# PacBot_Official_Schematic.net
KiCad netlist of a schematic drawn in EAGLE
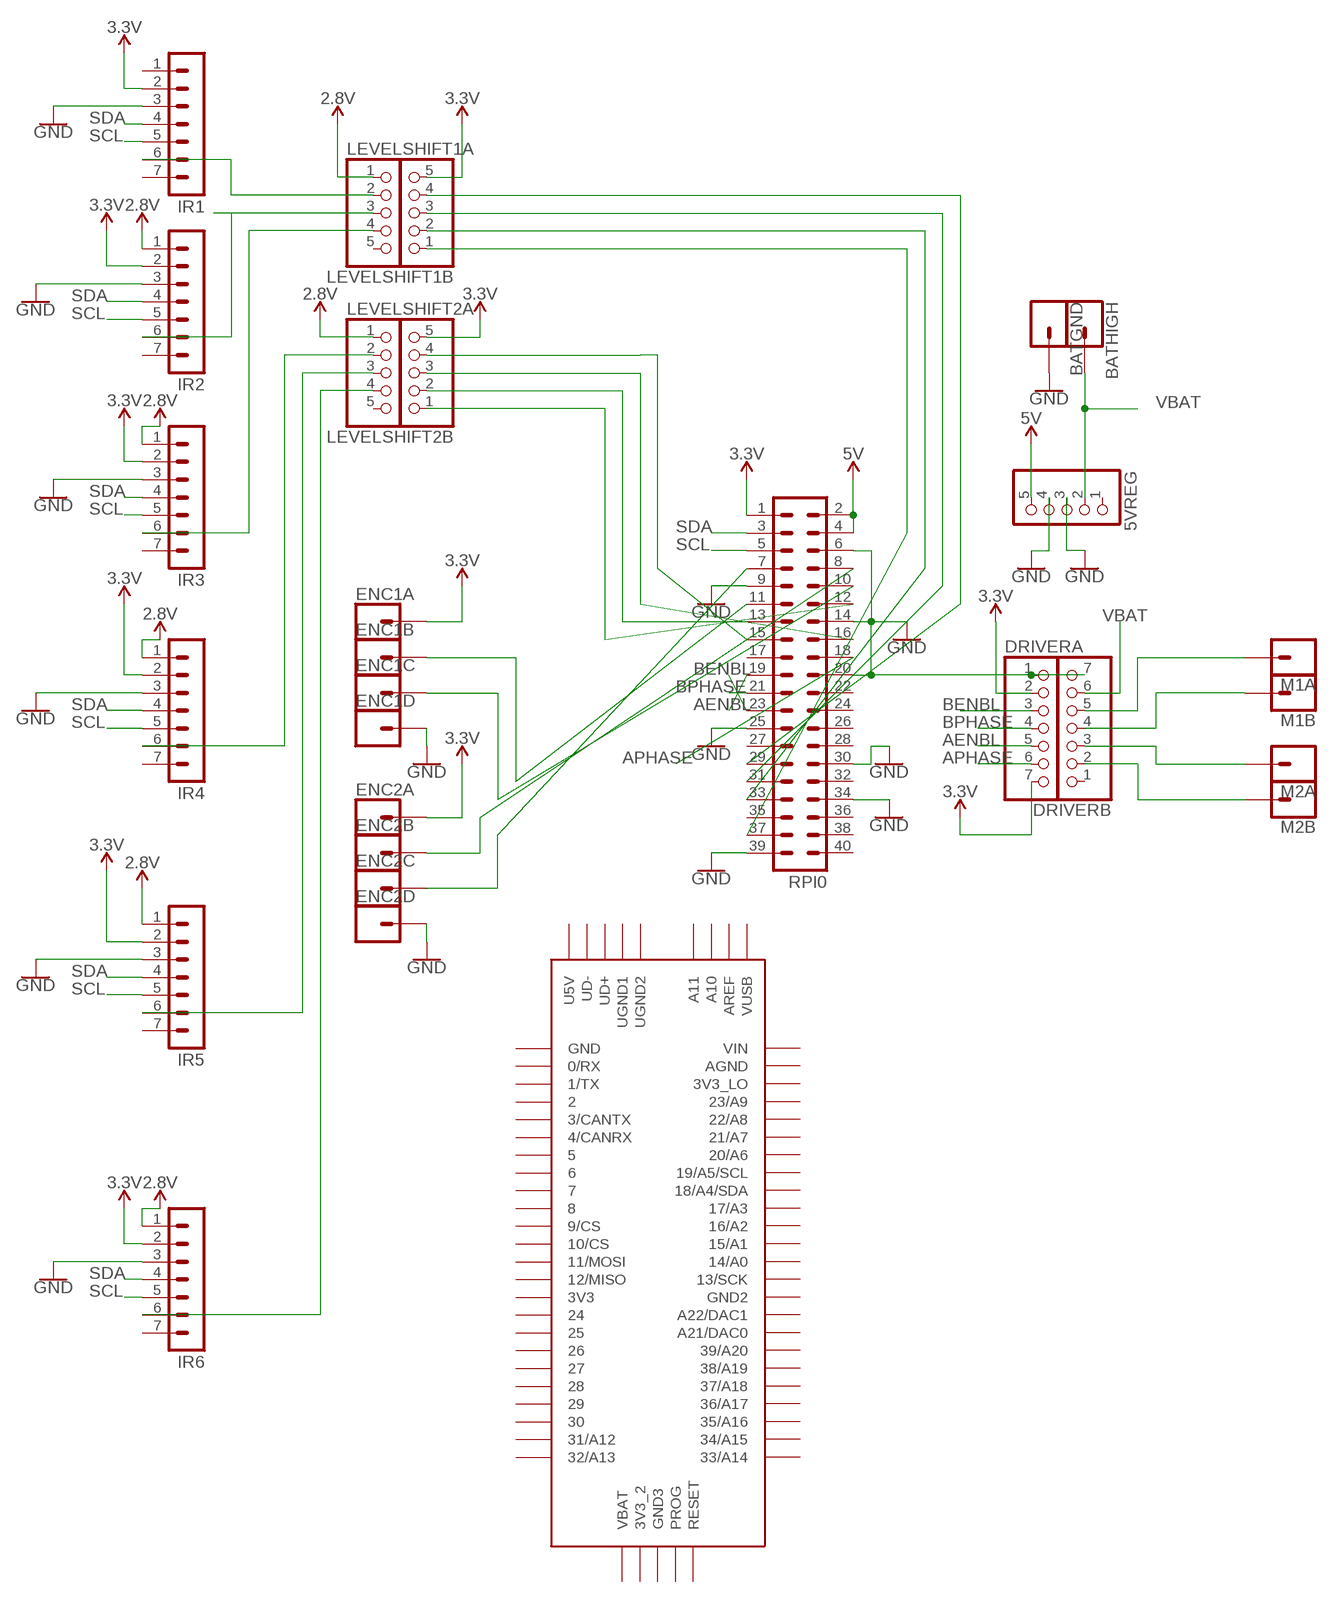
[diagram p0: schematic, sheet 1]

(export (version "E")
  (design (tool "Eeschema 10.0.6"))
  (components
    (comp (ref "5VREG")
      (value "PINHD-1X5")
      (footprint "eagle-import:1X05")
      (libsource (lib "eagle-import") (part "PINHD-1X5"))
    )
    (comp (ref "BATGND")
      (value "CONN_01")
      (footprint "eagle-import:1X01")
      (libsource (lib "eagle-import") (part "CONN_01"))
    )
    (comp (ref "BATHIGH")
      (value "CONN_01")
      (footprint "eagle-import:1X01")
      (libsource (lib "eagle-import") (part "CONN_01"))
    )
    (comp (ref "DRIVERA")
      (value "PINHD-1X7")
      (footprint "eagle-import:1X07")
      (libsource (lib "eagle-import") (part "PINHD-1X7"))
    )
    (comp (ref "DRIVERB")
      (value "PINHD-1X7")
      (footprint "eagle-import:1X07")
      (libsource (lib "eagle-import") (part "PINHD-1X7"))
    )
    (comp (ref "ENC1A")
      (value "CONN_01")
      (footprint "eagle-import:1X01")
      (libsource (lib "eagle-import") (part "CONN_01"))
    )
    (comp (ref "ENC1B")
      (value "CONN_01")
      (footprint "eagle-import:1X01")
      (libsource (lib "eagle-import") (part "CONN_01"))
    )
    (comp (ref "ENC1C")
      (value "CONN_01")
      (footprint "eagle-import:1X01")
      (libsource (lib "eagle-import") (part "CONN_01"))
    )
    (comp (ref "ENC1D")
      (value "CONN_01")
      (footprint "eagle-import:1X01")
      (libsource (lib "eagle-import") (part "CONN_01"))
    )
    (comp (ref "ENC2A")
      (value "CONN_01")
      (footprint "eagle-import:1X01")
      (libsource (lib "eagle-import") (part "CONN_01"))
    )
    (comp (ref "ENC2B")
      (value "CONN_01")
      (footprint "eagle-import:1X01")
      (libsource (lib "eagle-import") (part "CONN_01"))
    )
    (comp (ref "ENC2C")
      (value "CONN_01")
      (footprint "eagle-import:1X01")
      (libsource (lib "eagle-import") (part "CONN_01"))
    )
    (comp (ref "ENC2D")
      (value "CONN_01")
      (footprint "eagle-import:1X01")
      (libsource (lib "eagle-import") (part "CONN_01"))
    )
    (comp (ref "IR1")
      (value "MA07-1")
      (footprint "eagle-import:MA07-1")
      (libsource (lib "eagle-import") (part "MA07-1"))
    )
    (comp (ref "IR2")
      (value "MA07-1")
      (footprint "eagle-import:MA07-1")
      (libsource (lib "eagle-import") (part "MA07-1"))
    )
    (comp (ref "IR3")
      (value "MA07-1")
      (footprint "eagle-import:MA07-1")
      (libsource (lib "eagle-import") (part "MA07-1"))
    )
    (comp (ref "IR4")
      (value "MA07-1")
      (footprint "eagle-import:MA07-1")
      (libsource (lib "eagle-import") (part "MA07-1"))
    )
    (comp (ref "IR5")
      (value "MA07-1")
      (footprint "eagle-import:MA07-1")
      (libsource (lib "eagle-import") (part "MA07-1"))
    )
    (comp (ref "IR6")
      (value "MA07-1")
      (footprint "eagle-import:MA07-1")
      (libsource (lib "eagle-import") (part "MA07-1"))
    )
    (comp (ref "LEVELSHIFT1A")
      (value "PINHD-1X5")
      (footprint "eagle-import:1X05")
      (libsource (lib "eagle-import") (part "PINHD-1X5"))
    )
    (comp (ref "LEVELSHIFT1B")
      (value "PINHD-1X5")
      (footprint "eagle-import:1X05")
      (libsource (lib "eagle-import") (part "PINHD-1X5"))
    )
    (comp (ref "LEVELSHIFT2A")
      (value "PINHD-1X5")
      (footprint "eagle-import:1X05")
      (libsource (lib "eagle-import") (part "PINHD-1X5"))
    )
    (comp (ref "LEVELSHIFT2B")
      (value "PINHD-1X5")
      (footprint "eagle-import:1X05")
      (libsource (lib "eagle-import") (part "PINHD-1X5"))
    )
    (comp (ref "M1A")
      (value "CONN_01")
      (footprint "eagle-import:1X01")
      (libsource (lib "eagle-import") (part "CONN_01"))
    )
    (comp (ref "M1B")
      (value "CONN_01")
      (footprint "eagle-import:1X01")
      (libsource (lib "eagle-import") (part "CONN_01"))
    )
    (comp (ref "M2A")
      (value "CONN_01")
      (footprint "eagle-import:1X01")
      (libsource (lib "eagle-import") (part "CONN_01"))
    )
    (comp (ref "M2B")
      (value "CONN_01")
      (footprint "eagle-import:1X01")
      (libsource (lib "eagle-import") (part "CONN_01"))
    )
    (comp (ref "RPI0")
      (value "MA20-2")
      (footprint "eagle-import:MA20-2")
      (libsource (lib "eagle-import") (part "MA20-2"))
    )
    (comp (ref "U$1")
      (value "TEENSY_3.5/3.6")
      (footprint "eagle-import:TEENSY_3.5_3.6")
      (libsource (lib "eagle-import") (part "TEENSY_3.5/3.6"))
    )
  )
  (nets
    (net (code "1") (name "/AENBL") (class "Default")
      (node (ref "DRIVERA") (pin "5") (pinfunction "5_5") (pintype "passive"))
      (node (ref "RPI0") (pin "19") (pinfunction "19_19") (pintype "passive"))
    )
    (net (code "2") (name "/APHASE") (class "Default")
      (node (ref "DRIVERA") (pin "6") (pinfunction "6_6") (pintype "passive"))
      (node (ref "RPI0") (pin "18") (pinfunction "18_18") (pintype "passive"))
    )
    (net (code "3") (name "/BENBL") (class "Default")
      (node (ref "DRIVERA") (pin "3") (pinfunction "3_3") (pintype "passive"))
      (node (ref "RPI0") (pin "23") (pinfunction "23_23") (pintype "passive"))
    )
    (net (code "4") (name "/BPHASE") (class "Default")
      (node (ref "DRIVERA") (pin "4") (pinfunction "4_4") (pintype "passive"))
      (node (ref "RPI0") (pin "21") (pinfunction "21_21") (pintype "passive"))
    )
    (net (code "5") (name "/SCL") (class "Default")
      (node (ref "IR1") (pin "5") (pinfunction "5_5") (pintype "passive"))
      (node (ref "IR2") (pin "5") (pinfunction "5_5") (pintype "passive"))
      (node (ref "IR3") (pin "5") (pinfunction "5_5") (pintype "passive"))
      (node (ref "IR4") (pin "5") (pinfunction "5_5") (pintype "passive"))
      (node (ref "IR5") (pin "5") (pinfunction "5_5") (pintype "passive"))
      (node (ref "IR6") (pin "5") (pinfunction "5_5") (pintype "passive"))
      (node (ref "RPI0") (pin "5") (pinfunction "5_5") (pintype "passive"))
    )
    (net (code "6") (name "/SDA") (class "Default")
      (node (ref "IR1") (pin "4") (pinfunction "4_4") (pintype "passive"))
      (node (ref "IR2") (pin "4") (pinfunction "4_4") (pintype "passive"))
      (node (ref "IR3") (pin "4") (pinfunction "4_4") (pintype "passive"))
      (node (ref "IR4") (pin "4") (pinfunction "4_4") (pintype "passive"))
      (node (ref "IR5") (pin "4") (pinfunction "4_4") (pintype "passive"))
      (node (ref "IR6") (pin "4") (pinfunction "4_4") (pintype "passive"))
      (node (ref "RPI0") (pin "3") (pinfunction "3_3") (pintype "passive"))
    )
    (net (code "7") (name "/VBAT") (class "Default")
      (node (ref "5VREG") (pin "2") (pinfunction "2_2") (pintype "passive"))
      (node (ref "BATHIGH") (pin "1") (pinfunction "1_1") (pintype "passive"))
      (node (ref "DRIVERB") (pin "6") (pinfunction "6_6") (pintype "passive"))
    )
    (net (code "8") (name "2.8V") (class "Default")
      (node (ref "IR2") (pin "1") (pinfunction "1_1") (pintype "passive"))
      (node (ref "IR3") (pin "1") (pinfunction "1_1") (pintype "passive"))
      (node (ref "IR4") (pin "1") (pinfunction "1_1") (pintype "passive"))
      (node (ref "IR5") (pin "1") (pinfunction "1_1") (pintype "passive"))
      (node (ref "IR6") (pin "1") (pinfunction "1_1") (pintype "passive"))
      (node (ref "LEVELSHIFT1A") (pin "1") (pinfunction "1_1") (pintype "passive"))
      (node (ref "LEVELSHIFT2A") (pin "1") (pinfunction "1_1") (pintype "passive"))
    )
    (net (code "9") (name "3.3V") (class "Default")
      (node (ref "DRIVERA") (pin "2") (pinfunction "2_2") (pintype "passive"))
      (node (ref "DRIVERA") (pin "7") (pinfunction "7_7") (pintype "passive"))
      (node (ref "ENC1A") (pin "1") (pinfunction "1_1") (pintype "passive"))
      (node (ref "ENC2A") (pin "1") (pinfunction "1_1") (pintype "passive"))
      (node (ref "IR1") (pin "2") (pinfunction "2_2") (pintype "passive"))
      (node (ref "IR2") (pin "2") (pinfunction "2_2") (pintype "passive"))
      (node (ref "IR3") (pin "2") (pinfunction "2_2") (pintype "passive"))
      (node (ref "IR4") (pin "2") (pinfunction "2_2") (pintype "passive"))
      (node (ref "IR5") (pin "2") (pinfunction "2_2") (pintype "passive"))
      (node (ref "IR6") (pin "2") (pinfunction "2_2") (pintype "passive"))
      (node (ref "LEVELSHIFT1B") (pin "5") (pinfunction "5_5") (pintype "passive"))
      (node (ref "LEVELSHIFT2B") (pin "5") (pinfunction "5_5") (pintype "passive"))
      (node (ref "RPI0") (pin "1") (pinfunction "1_1") (pintype "passive"))
    )
    (net (code "10") (name "5V") (class "Default")
      (node (ref "5VREG") (pin "5") (pinfunction "5_5") (pintype "passive"))
      (node (ref "RPI0") (pin "2") (pinfunction "2_2") (pintype "passive"))
      (node (ref "RPI0") (pin "4") (pinfunction "4_4") (pintype "passive"))
    )
    (net (code "11") (name "GND") (class "Default")
      (node (ref "5VREG") (pin "3") (pinfunction "3_3") (pintype "passive"))
      (node (ref "5VREG") (pin "4") (pinfunction "4_4") (pintype "passive"))
      (node (ref "BATGND") (pin "1") (pinfunction "1_1") (pintype "passive"))
      (node (ref "DRIVERA") (pin "1") (pinfunction "1_1") (pintype "passive"))
      (node (ref "DRIVERB") (pin "7") (pinfunction "7_7") (pintype "passive"))
      (node (ref "ENC1D") (pin "1") (pinfunction "1_1") (pintype "passive"))
      (node (ref "ENC2D") (pin "1") (pinfunction "1_1") (pintype "passive"))
      (node (ref "IR1") (pin "3") (pinfunction "3_3") (pintype "passive"))
      (node (ref "IR2") (pin "3") (pinfunction "3_3") (pintype "passive"))
      (node (ref "IR3") (pin "3") (pinfunction "3_3") (pintype "passive"))
      (node (ref "IR4") (pin "3") (pinfunction "3_3") (pintype "passive"))
      (node (ref "IR5") (pin "3") (pinfunction "3_3") (pintype "passive"))
      (node (ref "IR6") (pin "3") (pinfunction "3_3") (pintype "passive"))
      (node (ref "RPI0") (pin "14") (pinfunction "14_14") (pintype "passive"))
      (node (ref "RPI0") (pin "20") (pinfunction "20_20") (pintype "passive"))
      (node (ref "RPI0") (pin "25") (pinfunction "25_25") (pintype "passive"))
      (node (ref "RPI0") (pin "30") (pinfunction "30_30") (pintype "passive"))
      (node (ref "RPI0") (pin "34") (pinfunction "34_34") (pintype "passive"))
      (node (ref "RPI0") (pin "39") (pinfunction "39_39") (pintype "passive"))
      (node (ref "RPI0") (pin "6") (pinfunction "6_6") (pintype "passive"))
      (node (ref "RPI0") (pin "9") (pinfunction "9_9") (pintype "passive"))
    )
    (net (code "12") (name "Net-(DRIVERB-Pad2)") (class "Default")
      (node (ref "DRIVERB") (pin "2") (pinfunction "2_2") (pintype "passive"))
      (node (ref "M2B") (pin "1") (pinfunction "1_1") (pintype "passive"))
    )
    (net (code "13") (name "Net-(DRIVERB-Pad3)") (class "Default")
      (node (ref "DRIVERB") (pin "3") (pinfunction "3_3") (pintype "passive"))
      (node (ref "M2A") (pin "1") (pinfunction "1_1") (pintype "passive"))
    )
    (net (code "14") (name "Net-(DRIVERB-Pad4)") (class "Default")
      (node (ref "DRIVERB") (pin "4") (pinfunction "4_4") (pintype "passive"))
      (node (ref "M1B") (pin "1") (pinfunction "1_1") (pintype "passive"))
    )
    (net (code "15") (name "Net-(DRIVERB-Pad5)") (class "Default")
      (node (ref "DRIVERB") (pin "5") (pinfunction "5_5") (pintype "passive"))
      (node (ref "M1A") (pin "1") (pinfunction "1_1") (pintype "passive"))
    )
    (net (code "16") (name "Net-(ENC1B-Pad1)") (class "Default")
      (node (ref "ENC1B") (pin "1") (pinfunction "1_1") (pintype "passive"))
      (node (ref "RPI0") (pin "11") (pinfunction "11_11") (pintype "passive"))
    )
    (net (code "17") (name "Net-(ENC1C-Pad1)") (class "Default")
      (node (ref "ENC1C") (pin "1") (pinfunction "1_1") (pintype "passive"))
      (node (ref "RPI0") (pin "10") (pinfunction "10_10") (pintype "passive"))
    )
    (net (code "18") (name "Net-(ENC2B-Pad1)") (class "Default")
      (node (ref "ENC2B") (pin "1") (pinfunction "1_1") (pintype "passive"))
      (node (ref "RPI0") (pin "8") (pinfunction "8_8") (pintype "passive"))
    )
    (net (code "19") (name "Net-(ENC2C-Pad1)") (class "Default")
      (node (ref "ENC2C") (pin "1") (pinfunction "1_1") (pintype "passive"))
      (node (ref "RPI0") (pin "7") (pinfunction "7_7") (pintype "passive"))
    )
    (net (code "20") (name "Net-(IR1-Pad6)") (class "Default")
      (node (ref "IR1") (pin "6") (pinfunction "6_6") (pintype "passive"))
      (node (ref "LEVELSHIFT1A") (pin "2") (pinfunction "2_2") (pintype "passive"))
    )
    (net (code "21") (name "Net-(IR3-Pad6)") (class "Default")
      (node (ref "IR3") (pin "6") (pinfunction "6_6") (pintype "passive"))
      (node (ref "LEVELSHIFT1A") (pin "4") (pinfunction "4_4") (pintype "passive"))
    )
    (net (code "22") (name "Net-(IR4-Pad6)") (class "Default")
      (node (ref "IR4") (pin "6") (pinfunction "6_6") (pintype "passive"))
      (node (ref "LEVELSHIFT2A") (pin "2") (pinfunction "2_2") (pintype "passive"))
    )
    (net (code "23") (name "Net-(IR5-Pad6)") (class "Default")
      (node (ref "IR5") (pin "6") (pinfunction "6_6") (pintype "passive"))
      (node (ref "LEVELSHIFT2A") (pin "3") (pinfunction "3_3") (pintype "passive"))
    )
    (net (code "24") (name "Net-(IR6-Pad6)") (class "Default")
      (node (ref "IR6") (pin "6") (pinfunction "6_6") (pintype "passive"))
      (node (ref "LEVELSHIFT2A") (pin "4") (pinfunction "4_4") (pintype "passive"))
    )
    (net (code "25") (name "Net-(LEVELSHIFT1B-Pad1)") (class "Default")
      (node (ref "LEVELSHIFT1B") (pin "1") (pinfunction "1_1") (pintype "passive"))
      (node (ref "RPI0") (pin "37") (pinfunction "37_37") (pintype "passive"))
    )
    (net (code "26") (name "Net-(LEVELSHIFT1B-Pad2)") (class "Default")
      (node (ref "LEVELSHIFT1B") (pin "2") (pinfunction "2_2") (pintype "passive"))
      (node (ref "RPI0") (pin "33") (pinfunction "33_33") (pintype "passive"))
    )
    (net (code "27") (name "Net-(LEVELSHIFT1B-Pad3)") (class "Default")
      (node (ref "LEVELSHIFT1B") (pin "3") (pinfunction "3_3") (pintype "passive"))
      (node (ref "RPI0") (pin "31") (pinfunction "31_31") (pintype "passive"))
    )
    (net (code "28") (name "Net-(LEVELSHIFT1B-Pad4)") (class "Default")
      (node (ref "LEVELSHIFT1B") (pin "4") (pinfunction "4_4") (pintype "passive"))
      (node (ref "RPI0") (pin "29") (pinfunction "29_29") (pintype "passive"))
    )
    (net (code "29") (name "Net-(LEVELSHIFT2B-Pad1)") (class "Default")
      (node (ref "LEVELSHIFT2B") (pin "1") (pinfunction "1_1") (pintype "passive"))
      (node (ref "RPI0") (pin "12") (pinfunction "12_12") (pintype "passive"))
    )
    (net (code "30") (name "Net-(LEVELSHIFT2B-Pad2)") (class "Default")
      (node (ref "LEVELSHIFT2B") (pin "2") (pinfunction "2_2") (pintype "passive"))
      (node (ref "RPI0") (pin "13") (pinfunction "13_13") (pintype "passive"))
    )
    (net (code "31") (name "Net-(LEVELSHIFT2B-Pad3)") (class "Default")
      (node (ref "LEVELSHIFT2B") (pin "3") (pinfunction "3_3") (pintype "passive"))
      (node (ref "RPI0") (pin "16") (pinfunction "16_16") (pintype "passive"))
    )
    (net (code "32") (name "Net-(LEVELSHIFT2B-Pad4)") (class "Default")
      (node (ref "LEVELSHIFT2B") (pin "4") (pinfunction "4_4") (pintype "passive"))
      (node (ref "RPI0") (pin "15") (pinfunction "15_15") (pintype "passive"))
    )
    (net (code "33") (name "unconnected-(5VREG-Pad1)") (class "Default")
      (node (ref "5VREG") (pin "1") (pinfunction "1_1") (pintype "passive"))
    )
    (net (code "34") (name "unconnected-(DRIVERB-Pad1)") (class "Default")
      (node (ref "DRIVERB") (pin "1") (pinfunction "1_1") (pintype "passive"))
    )
    (net (code "35") (name "unconnected-(IR1-Pad1)") (class "Default")
      (node (ref "IR1") (pin "1") (pinfunction "1_1") (pintype "passive"))
    )
    (net (code "36") (name "unconnected-(IR1-Pad7)") (class "Default")
      (node (ref "IR1") (pin "7") (pinfunction "7_7") (pintype "passive"))
    )
    (net (code "37") (name "unconnected-(IR2-Pad6)") (class "Default")
      (node (ref "IR2") (pin "6") (pinfunction "6_6") (pintype "passive"))
    )
    (net (code "38") (name "unconnected-(IR2-Pad7)") (class "Default")
      (node (ref "IR2") (pin "7") (pinfunction "7_7") (pintype "passive"))
    )
    (net (code "39") (name "unconnected-(IR3-Pad7)") (class "Default")
      (node (ref "IR3") (pin "7") (pinfunction "7_7") (pintype "passive"))
    )
    (net (code "40") (name "unconnected-(IR4-Pad7)") (class "Default")
      (node (ref "IR4") (pin "7") (pinfunction "7_7") (pintype "passive"))
    )
    (net (code "41") (name "unconnected-(IR5-Pad7)") (class "Default")
      (node (ref "IR5") (pin "7") (pinfunction "7_7") (pintype "passive"))
    )
    (net (code "42") (name "unconnected-(IR6-Pad7)") (class "Default")
      (node (ref "IR6") (pin "7") (pinfunction "7_7") (pintype "passive"))
    )
    (net (code "43") (name "unconnected-(LEVELSHIFT1A-Pad3)") (class "Default")
      (node (ref "LEVELSHIFT1A") (pin "3") (pinfunction "3_3") (pintype "passive"))
    )
    (net (code "44") (name "unconnected-(LEVELSHIFT1A-Pad5)") (class "Default")
      (node (ref "LEVELSHIFT1A") (pin "5") (pinfunction "5_5") (pintype "passive"))
    )
    (net (code "45") (name "unconnected-(LEVELSHIFT2A-Pad5)") (class "Default")
      (node (ref "LEVELSHIFT2A") (pin "5") (pinfunction "5_5") (pintype "passive"))
    )
    (net (code "46") (name "unconnected-(RPI0-Pad17)") (class "Default")
      (node (ref "RPI0") (pin "17") (pinfunction "17_17") (pintype "passive"))
    )
    (net (code "47") (name "unconnected-(RPI0-Pad22)") (class "Default")
      (node (ref "RPI0") (pin "22") (pinfunction "22_22") (pintype "passive"))
    )
    (net (code "48") (name "unconnected-(RPI0-Pad24)") (class "Default")
      (node (ref "RPI0") (pin "24") (pinfunction "24_24") (pintype "passive"))
    )
    (net (code "49") (name "unconnected-(RPI0-Pad26)") (class "Default")
      (node (ref "RPI0") (pin "26") (pinfunction "26_26") (pintype "passive"))
    )
    (net (code "50") (name "unconnected-(RPI0-Pad27)") (class "Default")
      (node (ref "RPI0") (pin "27") (pinfunction "27_27") (pintype "passive"))
    )
    (net (code "51") (name "unconnected-(RPI0-Pad28)") (class "Default")
      (node (ref "RPI0") (pin "28") (pinfunction "28_28") (pintype "passive"))
    )
    (net (code "52") (name "unconnected-(RPI0-Pad32)") (class "Default")
      (node (ref "RPI0") (pin "32") (pinfunction "32_32") (pintype "passive"))
    )
    (net (code "53") (name "unconnected-(RPI0-Pad35)") (class "Default")
      (node (ref "RPI0") (pin "35") (pinfunction "35_35") (pintype "passive"))
    )
    (net (code "54") (name "unconnected-(RPI0-Pad36)") (class "Default")
      (node (ref "RPI0") (pin "36") (pinfunction "36_36") (pintype "passive"))
    )
    (net (code "55") (name "unconnected-(RPI0-Pad38)") (class "Default")
      (node (ref "RPI0") (pin "38") (pinfunction "38_38") (pintype "passive"))
    )
    (net (code "56") (name "unconnected-(RPI0-Pad40)") (class "Default")
      (node (ref "RPI0") (pin "40") (pinfunction "40_40") (pintype "passive"))
    )
    (net (code "57") (name "unconnected-(U$1-A21{slash}DAC0-Pad21{slash}DAC0)") (class "Default")
      (node (ref "U$1") (pin "21/DAC0") (pinfunction "A21/DAC0_21/DAC0") (pintype "bidirectional"))
    )
    (net (code "58") (name "unconnected-(U$1-Pad0{slash}RX)") (class "Default")
      (node (ref "U$1") (pin "0/RX") (pinfunction "0/RX_0/RX") (pintype "bidirectional"))
    )
    (net (code "59") (name "unconnected-(U$1-Pad1{slash}TX)") (class "Default")
      (node (ref "U$1") (pin "1/TX") (pinfunction "1/TX_1/TX") (pintype "bidirectional"))
    )
    (net (code "60") (name "unconnected-(U$1-Pad2)") (class "Default")
      (node (ref "U$1") (pin "2") (pinfunction "2_2") (pintype "bidirectional"))
    )
    (net (code "61") (name "unconnected-(U$1-Pad3V3)") (class "Default")
      (node (ref "U$1") (pin "3V3") (pinfunction "3V3_3V3") (pintype "bidirectional"))
    )
    (net (code "62") (name "unconnected-(U$1-Pad3V3_2)") (class "Default")
      (node (ref "U$1") (pin "3V3_2") (pinfunction "3V3_2_3V3_2") (pintype "bidirectional"))
    )
    (net (code "63") (name "unconnected-(U$1-Pad3V3_LO)") (class "Default")
      (node (ref "U$1") (pin "3V3_LO") (pinfunction "3V3_LO_3V3_LO") (pintype "bidirectional"))
    )
    (net (code "64") (name "unconnected-(U$1-Pad3{slash}CANTX)") (class "Default")
      (node (ref "U$1") (pin "3/CANTX") (pinfunction "3/CANTX_3/CANTX") (pintype "bidirectional"))
    )
    (net (code "65") (name "unconnected-(U$1-Pad4{slash}CANRX)") (class "Default")
      (node (ref "U$1") (pin "4/CANRX") (pinfunction "4/CANRX_4/CANRX") (pintype "bidirectional"))
    )
    (net (code "66") (name "unconnected-(U$1-Pad5)") (class "Default")
      (node (ref "U$1") (pin "5") (pinfunction "5_5") (pintype "bidirectional"))
    )
    (net (code "67") (name "unconnected-(U$1-Pad6)") (class "Default")
      (node (ref "U$1") (pin "6") (pinfunction "6_6") (pintype "bidirectional"))
    )
    (net (code "68") (name "unconnected-(U$1-Pad7)") (class "Default")
      (node (ref "U$1") (pin "7") (pinfunction "7_7") (pintype "bidirectional"))
    )
    (net (code "69") (name "unconnected-(U$1-Pad8)") (class "Default")
      (node (ref "U$1") (pin "8") (pinfunction "8_8") (pintype "bidirectional"))
    )
    (net (code "70") (name "unconnected-(U$1-Pad9{slash}CS)") (class "Default")
      (node (ref "U$1") (pin "9/CS") (pinfunction "9/CS_9/CS") (pintype "bidirectional"))
    )
    (net (code "71") (name "unconnected-(U$1-Pad10{slash}CS)") (class "Default")
      (node (ref "U$1") (pin "10/CS") (pinfunction "10/CS_10/CS") (pintype "bidirectional"))
    )
    (net (code "72") (name "unconnected-(U$1-Pad11{slash}MOSI)") (class "Default")
      (node (ref "U$1") (pin "11/MOSI") (pinfunction "11/MOSI_11/MOSI") (pintype "bidirectional"))
    )
    (net (code "73") (name "unconnected-(U$1-Pad12{slash}MISO)") (class "Default")
      (node (ref "U$1") (pin "12/MISO") (pinfunction "12/MISO_12/MISO") (pintype "bidirectional"))
    )
    (net (code "74") (name "unconnected-(U$1-Pad13{slash}SCK)") (class "Default")
      (node (ref "U$1") (pin "13/SCK") (pinfunction "13/SCK_13/SCK") (pintype "bidirectional"))
    )
    (net (code "75") (name "unconnected-(U$1-Pad14{slash}A0)") (class "Default")
      (node (ref "U$1") (pin "14/A0") (pinfunction "14/A0_14/A0") (pintype "bidirectional"))
    )
    (net (code "76") (name "unconnected-(U$1-Pad15{slash}A1)") (class "Default")
      (node (ref "U$1") (pin "15/A1") (pinfunction "15/A1_15/A1") (pintype "bidirectional"))
    )
    (net (code "77") (name "unconnected-(U$1-Pad16{slash}A2)") (class "Default")
      (node (ref "U$1") (pin "16/A2") (pinfunction "16/A2_16/A2") (pintype "bidirectional"))
    )
    (net (code "78") (name "unconnected-(U$1-Pad17{slash}A3)") (class "Default")
      (node (ref "U$1") (pin "17/A3") (pinfunction "17/A3_17/A3") (pintype "bidirectional"))
    )
    (net (code "79") (name "unconnected-(U$1-Pad18{slash}A4{slash}SDA)") (class "Default")
      (node (ref "U$1") (pin "18/A4/SDA") (pinfunction "18/A4/SDA_18/A4/SDA") (pintype "bidirectional"))
    )
    (net (code "80") (name "unconnected-(U$1-Pad19{slash}A5{slash}SCL)") (class "Default")
      (node (ref "U$1") (pin "19/A5/SCL") (pinfunction "19/A5/SCL_19/A5/SCL") (pintype "bidirectional"))
    )
    (net (code "81") (name "unconnected-(U$1-Pad20{slash}A6)") (class "Default")
      (node (ref "U$1") (pin "20/A6") (pinfunction "20/A6_20/A6") (pintype "bidirectional"))
    )
    (net (code "82") (name "unconnected-(U$1-Pad21{slash}A7)") (class "Default")
      (node (ref "U$1") (pin "21/A7") (pinfunction "21/A7_21/A7") (pintype "bidirectional"))
    )
    (net (code "83") (name "unconnected-(U$1-Pad22{slash}A8)") (class "Default")
      (node (ref "U$1") (pin "22/A8") (pinfunction "22/A8_22/A8") (pintype "bidirectional"))
    )
    (net (code "84") (name "unconnected-(U$1-Pad23{slash}A9)") (class "Default")
      (node (ref "U$1") (pin "23/A9") (pinfunction "23/A9_23/A9") (pintype "bidirectional"))
    )
    (net (code "85") (name "unconnected-(U$1-Pad24)") (class "Default")
      (node (ref "U$1") (pin "24") (pinfunction "24_24") (pintype "bidirectional"))
    )
    (net (code "86") (name "unconnected-(U$1-Pad25)") (class "Default")
      (node (ref "U$1") (pin "25") (pinfunction "25_25") (pintype "bidirectional"))
    )
    (net (code "87") (name "unconnected-(U$1-Pad26)") (class "Default")
      (node (ref "U$1") (pin "26") (pinfunction "26_26") (pintype "bidirectional"))
    )
    (net (code "88") (name "unconnected-(U$1-Pad27)") (class "Default")
      (node (ref "U$1") (pin "27") (pinfunction "27_27") (pintype "bidirectional"))
    )
    (net (code "89") (name "unconnected-(U$1-Pad28)") (class "Default")
      (node (ref "U$1") (pin "28") (pinfunction "28_28") (pintype "bidirectional"))
    )
    (net (code "90") (name "unconnected-(U$1-Pad29)") (class "Default")
      (node (ref "U$1") (pin "29") (pinfunction "29_29") (pintype "bidirectional"))
    )
    (net (code "91") (name "unconnected-(U$1-Pad30)") (class "Default")
      (node (ref "U$1") (pin "30") (pinfunction "30_30") (pintype "bidirectional"))
    )
    (net (code "92") (name "unconnected-(U$1-Pad31{slash}A12)") (class "Default")
      (node (ref "U$1") (pin "31/A12") (pinfunction "31/A12_31/A12") (pintype "bidirectional"))
    )
    (net (code "93") (name "unconnected-(U$1-Pad32{slash}A13)") (class "Default")
      (node (ref "U$1") (pin "32/A13") (pinfunction "32/A13_32/A13") (pintype "bidirectional"))
    )
    (net (code "94") (name "unconnected-(U$1-Pad33{slash}A14)") (class "Default")
      (node (ref "U$1") (pin "33/A14") (pinfunction "33/A14_33/A14") (pintype "bidirectional"))
    )
    (net (code "95") (name "unconnected-(U$1-Pad34{slash}A15)") (class "Default")
      (node (ref "U$1") (pin "34/A15") (pinfunction "34/A15_34/A15") (pintype "bidirectional"))
    )
    (net (code "96") (name "unconnected-(U$1-Pad35{slash}A16)") (class "Default")
      (node (ref "U$1") (pin "35/A16") (pinfunction "35/A16_35/A16") (pintype "bidirectional"))
    )
    (net (code "97") (name "unconnected-(U$1-Pad36{slash}A17)") (class "Default")
      (node (ref "U$1") (pin "36/A17") (pinfunction "36/A17_36/A17") (pintype "bidirectional"))
    )
    (net (code "98") (name "unconnected-(U$1-Pad37{slash}A18)") (class "Default")
      (node (ref "U$1") (pin "37/A18") (pinfunction "37/A18_37/A18") (pintype "bidirectional"))
    )
    (net (code "99") (name "unconnected-(U$1-Pad38{slash}A19)") (class "Default")
      (node (ref "U$1") (pin "38/A19") (pinfunction "38/A19_38/A19") (pintype "bidirectional"))
    )
    (net (code "100") (name "unconnected-(U$1-Pad39{slash}A20)") (class "Default")
      (node (ref "U$1") (pin "39/A20") (pinfunction "39/A20_39/A20") (pintype "bidirectional"))
    )
    (net (code "101") (name "unconnected-(U$1-PadA10)") (class "Default")
      (node (ref "U$1") (pin "A10") (pinfunction "A10_A10") (pintype "bidirectional"))
    )
    (net (code "102") (name "unconnected-(U$1-PadA11)") (class "Default")
      (node (ref "U$1") (pin "A11") (pinfunction "A11_A11") (pintype "bidirectional"))
    )
    (net (code "103") (name "unconnected-(U$1-PadA22{slash}DAC1)") (class "Default")
      (node (ref "U$1") (pin "A22/DAC1") (pinfunction "A22/DAC1_A22/DAC1") (pintype "bidirectional"))
    )
    (net (code "104") (name "unconnected-(U$1-PadAGND)") (class "Default")
      (node (ref "U$1") (pin "AGND") (pinfunction "AGND_AGND") (pintype "bidirectional"))
    )
    (net (code "105") (name "unconnected-(U$1-PadAREF)") (class "Default")
      (node (ref "U$1") (pin "AREF") (pinfunction "AREF_AREF") (pintype "bidirectional"))
    )
    (net (code "106") (name "unconnected-(U$1-PadGND)") (class "Default")
      (node (ref "U$1") (pin "GND") (pinfunction "GND_GND") (pintype "bidirectional"))
    )
    (net (code "107") (name "unconnected-(U$1-PadGND2)") (class "Default")
      (node (ref "U$1") (pin "GND2") (pinfunction "GND2_GND2") (pintype "bidirectional"))
    )
    (net (code "108") (name "unconnected-(U$1-PadGND3)") (class "Default")
      (node (ref "U$1") (pin "GND3") (pinfunction "GND3_GND3") (pintype "bidirectional"))
    )
    (net (code "109") (name "unconnected-(U$1-PadPROG)") (class "Default")
      (node (ref "U$1") (pin "PROG") (pinfunction "PROG_PROG") (pintype "bidirectional"))
    )
    (net (code "110") (name "unconnected-(U$1-PadRESET)") (class "Default")
      (node (ref "U$1") (pin "RESET") (pinfunction "RESET_RESET") (pintype "bidirectional"))
    )
    (net (code "111") (name "unconnected-(U$1-PadU5V)") (class "Default")
      (node (ref "U$1") (pin "U5V") (pinfunction "U5V_U5V") (pintype "bidirectional"))
    )
    (net (code "112") (name "unconnected-(U$1-PadUD+)") (class "Default")
      (node (ref "U$1") (pin "UD+") (pinfunction "UD+_UD+") (pintype "bidirectional"))
    )
    (net (code "113") (name "unconnected-(U$1-PadUD-)") (class "Default")
      (node (ref "U$1") (pin "UD-") (pinfunction "UD-_UD-") (pintype "bidirectional"))
    )
    (net (code "114") (name "unconnected-(U$1-PadUGND1)") (class "Default")
      (node (ref "U$1") (pin "UGND1") (pinfunction "UGND1_UGND1") (pintype "bidirectional"))
    )
    (net (code "115") (name "unconnected-(U$1-PadUGND2)") (class "Default")
      (node (ref "U$1") (pin "UGND2") (pinfunction "UGND2_UGND2") (pintype "bidirectional"))
    )
    (net (code "116") (name "unconnected-(U$1-PadVBAT)") (class "Default")
      (node (ref "U$1") (pin "VBAT") (pinfunction "VBAT_VBAT") (pintype "bidirectional"))
    )
    (net (code "117") (name "unconnected-(U$1-PadVIN)") (class "Default")
      (node (ref "U$1") (pin "VIN") (pinfunction "VIN_VIN") (pintype "bidirectional"))
    )
    (net (code "118") (name "unconnected-(U$1-PadVUSB)") (class "Default")
      (node (ref "U$1") (pin "VUSB") (pinfunction "VUSB_VUSB") (pintype "bidirectional"))
    )
  )
)
